# pi_powersupply.net
KiCad netlist of a schematic drawn in Altium Designer
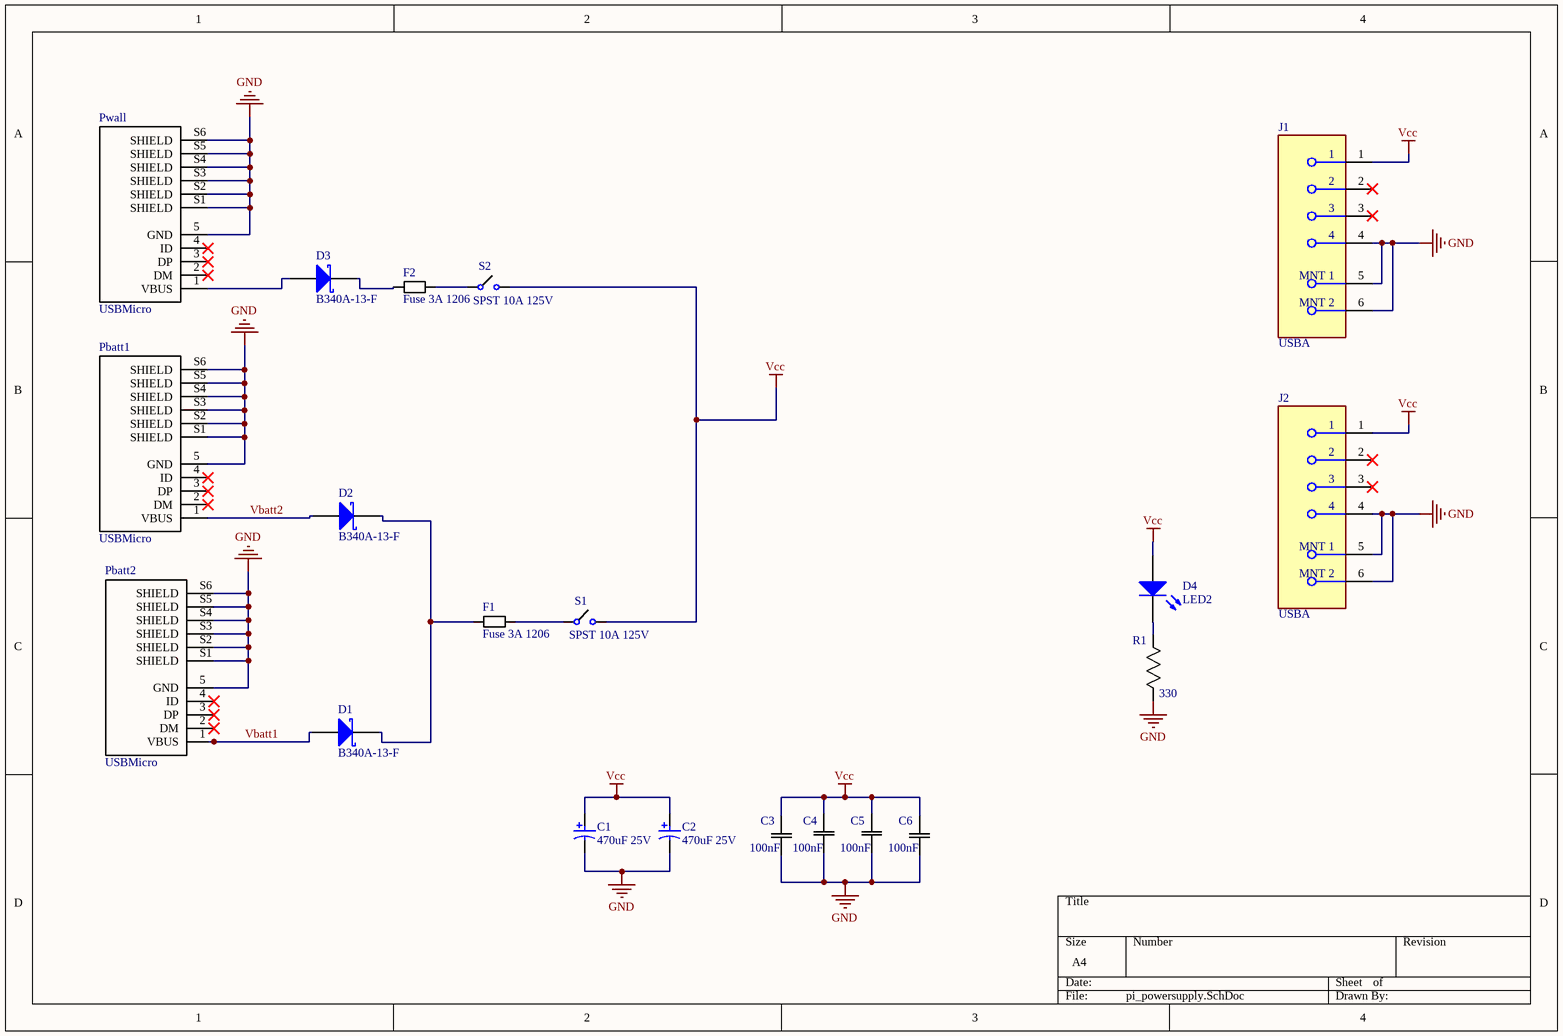
[diagram p0: pi_powersupply.SchDoc]

(export (version "E")
  (design (tool "Eeschema 10.0.6"))
  (components
    (comp (ref "C1")
      (value "470uF 25V")
      (footprint "NIC-CAPA2-10X10_V")
      (fields (field (name "PARTNUMBER") "UUD1E471MNL1GS") (field (name "MANUFACTURER") "Nichicon"))
      (libsource (lib "Altium Content Vault") (part "NIC-CAP-P-2"))
    )
    (comp (ref "C2")
      (value "470uF 25V")
      (footprint "NIC-CAPA2-10X10_V")
      (fields (field (name "PARTNUMBER") "UUD1E471MNL1GS") (field (name "MANUFACTURER") "Nichicon"))
      (libsource (lib "Altium Content Vault") (part "NIC-CAP-P-2"))
    )
    (comp (ref "C3")
      (value "100nF")
      (footprint "0805")
      (description "CAP CER 0.1UF 50V X7R 0805")
      (fields (field (name "MP") "CC0805KRX7R9BB104") (field (name "MF") "Yageo"))
      (libsource (lib "AltiumLibraries") (part "CAP 100nF 0805"))
    )
    (comp (ref "C4")
      (value "100nF")
      (footprint "0805")
      (description "CAP CER 0.1UF 50V X7R 0805")
      (fields (field (name "MP") "CC0805KRX7R9BB104") (field (name "MF") "Yageo"))
      (libsource (lib "AltiumLibraries") (part "CAP 100nF 0805"))
    )
    (comp (ref "C5")
      (value "100nF")
      (footprint "0805")
      (description "CAP CER 0.1UF 50V X7R 0805")
      (fields (field (name "MP") "CC0805KRX7R9BB104") (field (name "MF") "Yageo"))
      (libsource (lib "AltiumLibraries") (part "CAP 100nF 0805"))
    )
    (comp (ref "C6")
      (value "100nF")
      (footprint "0805")
      (description "CAP CER 0.1UF 50V X7R 0805")
      (fields (field (name "MP") "CC0805KRX7R9BB104") (field (name "MF") "Yageo"))
      (libsource (lib "AltiumLibraries") (part "CAP 100nF 0805"))
    )
    (comp (ref "D1")
      (value "B340A-13-F")
      (footprint "DIOD-SMA-2_V")
      (libsource (lib "Altium Content Vault") (part "DSKY-AK-2"))
    )
    (comp (ref "D2")
      (value "B340A-13-F")
      (footprint "DIOD-SMA-2_V")
      (libsource (lib "Altium Content Vault") (part "DSKY-AK-2"))
    )
    (comp (ref "D3")
      (value "B340A-13-F")
      (footprint "DIOD-SMA-2_V")
      (libsource (lib "Altium Content Vault") (part "DSKY-AK-2"))
    )
    (comp (ref "D4")
      (value "LED2")
      (footprint "3.2X1.6X1.1")
      (description "Typical RED, GREEN, YELLOW, AMBER GaAs LED")
      (fields (field (name "MF") "Lite-On Inc.") (field (name "MP") "LTST-C190CKT"))
      (libsource (lib "AltiumLibraries") (part "LED RED SMD"))
    )
    (comp (ref "F1")
      (value "Fuse 3A 1206")
      (footprint "1206")
      (description "FUSE 3.0A 63VAC/DC SLOW 1206")
      (fields (field (name "MF") "Bel Fuse Inc.") (field (name "MP") "0685T3000-01"))
      (libsource (lib "AltiumLibraries") (part "Fuse 3A 1206"))
    )
    (comp (ref "F2")
      (value "Fuse 3A 1206")
      (footprint "1206")
      (description "FUSE 3.0A 63VAC/DC SLOW 1206")
      (fields (field (name "MF") "Bel Fuse Inc.") (field (name "MP") "0685T3000-01"))
      (libsource (lib "AltiumLibraries") (part "Fuse 3A 1206"))
    )
    (comp (ref "J1")
      (value "USBA")
      (footprint "TE_Connectivity_292303-4_MFG")
      (description "CONN RCPT USB2.0 TYPEA 4POS R/A")
      (fields (field (name "PART NUMBER") "292303-4") (field (name "MANUFACTURER") "TE Connectivity"))
      (libsource (lib "Altium Content Vault") (part "292303-4"))
    )
    (comp (ref "J2")
      (value "USBA")
      (footprint "TE_Connectivity_292303-4_MFG")
      (description "CONN RCPT USB2.0 TYPEA 4POS R/A")
      (fields (field (name "PART NUMBER") "292303-4") (field (name "MANUFACTURER") "TE Connectivity"))
      (libsource (lib "Altium Content Vault") (part "292303-4"))
    )
    (comp (ref "Pbatt1")
      (value "USBMicro")
      (footprint "USB Micro B Receptacle")
      (description "USB - micro B USB 2.0 Receptacle Connector 5 Position Surface Mount, Right Angle; Through Hole")
      (fields (field (name "MF") "Amphenol ICC (FCI)") (field (name "MP") "10118194-0001LF"))
      (libsource (lib "AltiumLibraries") (part "USB Micro B Receptacle"))
    )
    (comp (ref "Pbatt2")
      (value "USBMicro")
      (footprint "USB Micro B Receptacle")
      (description "USB - micro B USB 2.0 Receptacle Connector 5 Position Surface Mount, Right Angle; Through Hole")
      (fields (field (name "MF") "Amphenol ICC (FCI)") (field (name "MP") "10118194-0001LF"))
      (libsource (lib "AltiumLibraries") (part "USB Micro B Receptacle"))
    )
    (comp (ref "Pwall")
      (value "USBMicro")
      (footprint "USB Micro B Receptacle")
      (description "USB - micro B USB 2.0 Receptacle Connector 5 Position Surface Mount, Right Angle; Through Hole")
      (fields (field (name "MF") "Amphenol ICC (FCI)") (field (name "MP") "10118194-0001LF"))
      (libsource (lib "AltiumLibraries") (part "USB Micro B Receptacle"))
    )
    (comp (ref "R1")
      (value "330")
      (footprint "0805")
      (description "RES SMD 330 OHM 1% 1/8W 0805")
      (fields (field (name "MP") "RC0805FR-07330RL") (field (name "MF") "Yageo"))
      (libsource (lib "AltiumLibraries") (part "RES 330 0805"))
    )
    (comp (ref "S1")
      (value "SPST 10A 125V")
      (footprint "SWITCH ROCKER SPST 10A 125V")
      (description "Rocker Switch SPST 10A (AC) 125V Panel Mount, Snap-In")
      (fields (field (name "MP") "SRB22A2FBBNN") (field (name "MF") "ZF Electronics"))
      (libsource (lib "AltiumLibraries") (part "SW ROCKER"))
    )
    (comp (ref "S2")
      (value "SPST 10A 125V")
      (footprint "SWITCH ROCKER SPST 10A 125V")
      (description "Rocker Switch SPST 10A (AC) 125V Panel Mount, Snap-In")
      (fields (field (name "MP") "SRB22A2FBBNN") (field (name "MF") "ZF Electronics"))
      (libsource (lib "AltiumLibraries") (part "SW ROCKER"))
    )
  )
  (nets
    (net (code "1") (name "/Vbatt1") (class "Default")
      (node (ref "D1") (pin "1") (pinfunction "A_1") (pintype "passive"))
      (node (ref "Pbatt2") (pin "1") (pinfunction "VBUS_1") (pintype "passive"))
    )
    (net (code "2") (name "/Vbatt2") (class "Default")
      (node (ref "D2") (pin "1") (pinfunction "A_1") (pintype "passive"))
      (node (ref "Pbatt1") (pin "1") (pinfunction "VBUS_1") (pintype "passive"))
    )
    (net (code "3") (name "GND") (class "Default")
      (node (ref "C1") (pin "2") (pinfunction "2_2") (pintype "passive"))
      (node (ref "C2") (pin "2") (pinfunction "2_2") (pintype "passive"))
      (node (ref "C3") (pin "1") (pinfunction "C1_1") (pintype "passive"))
      (node (ref "C4") (pin "1") (pinfunction "C1_1") (pintype "passive"))
      (node (ref "C5") (pin "1") (pinfunction "C1_1") (pintype "passive"))
      (node (ref "C6") (pin "1") (pinfunction "C1_1") (pintype "passive"))
      (node (ref "J1") (pin "4") (pinfunction "4_4") (pintype "passive"))
      (node (ref "J1") (pin "5") (pinfunction "MNT_1_5") (pintype "passive"))
      (node (ref "J1") (pin "6") (pinfunction "MNT_2_6") (pintype "passive"))
      (node (ref "J2") (pin "4") (pinfunction "4_4") (pintype "passive"))
      (node (ref "J2") (pin "5") (pinfunction "MNT_1_5") (pintype "passive"))
      (node (ref "J2") (pin "6") (pinfunction "MNT_2_6") (pintype "passive"))
      (node (ref "Pbatt1") (pin "5") (pinfunction "GND_5") (pintype "passive"))
      (node (ref "Pbatt1") (pin "S1") (pinfunction "SHIELD_S1") (pintype "passive"))
      (node (ref "Pbatt1") (pin "S2") (pinfunction "SHIELD_S2") (pintype "passive"))
      (node (ref "Pbatt1") (pin "S3") (pinfunction "SHIELD_S3") (pintype "passive"))
      (node (ref "Pbatt1") (pin "S4") (pinfunction "SHIELD_S4") (pintype "passive"))
      (node (ref "Pbatt1") (pin "S5") (pinfunction "SHIELD_S5") (pintype "passive"))
      (node (ref "Pbatt1") (pin "S6") (pinfunction "SHIELD_S6") (pintype "passive"))
      (node (ref "Pbatt2") (pin "5") (pinfunction "GND_5") (pintype "passive"))
      (node (ref "Pbatt2") (pin "S1") (pinfunction "SHIELD_S1") (pintype "passive"))
      (node (ref "Pbatt2") (pin "S2") (pinfunction "SHIELD_S2") (pintype "passive"))
      (node (ref "Pbatt2") (pin "S3") (pinfunction "SHIELD_S3") (pintype "passive"))
      (node (ref "Pbatt2") (pin "S4") (pinfunction "SHIELD_S4") (pintype "passive"))
      (node (ref "Pbatt2") (pin "S5") (pinfunction "SHIELD_S5") (pintype "passive"))
      (node (ref "Pbatt2") (pin "S6") (pinfunction "SHIELD_S6") (pintype "passive"))
      (node (ref "Pwall") (pin "5") (pinfunction "GND_5") (pintype "passive"))
      (node (ref "Pwall") (pin "S1") (pinfunction "SHIELD_S1") (pintype "passive"))
      (node (ref "Pwall") (pin "S2") (pinfunction "SHIELD_S2") (pintype "passive"))
      (node (ref "Pwall") (pin "S3") (pinfunction "SHIELD_S3") (pintype "passive"))
      (node (ref "Pwall") (pin "S4") (pinfunction "SHIELD_S4") (pintype "passive"))
      (node (ref "Pwall") (pin "S5") (pinfunction "SHIELD_S5") (pintype "passive"))
      (node (ref "Pwall") (pin "S6") (pinfunction "SHIELD_S6") (pintype "passive"))
      (node (ref "R1") (pin "2") (pinfunction "R2_2") (pintype "passive"))
    )
    (net (code "4") (name "Net-(D1-K)") (class "Default")
      (node (ref "D1") (pin "2") (pinfunction "K_2") (pintype "passive"))
      (node (ref "D2") (pin "2") (pinfunction "K_2") (pintype "passive"))
      (node (ref "F1") (pin "1") (pinfunction "1_1") (pintype "passive"))
    )
    (net (code "5") (name "Net-(D3-A)") (class "Default")
      (node (ref "D3") (pin "1") (pinfunction "A_1") (pintype "passive"))
      (node (ref "Pwall") (pin "1") (pinfunction "VBUS_1") (pintype "passive"))
    )
    (net (code "6") (name "Net-(D3-K)") (class "Default")
      (node (ref "D3") (pin "2") (pinfunction "K_2") (pintype "passive"))
      (node (ref "F2") (pin "1") (pinfunction "1_1") (pintype "passive"))
    )
    (net (code "7") (name "Net-(D4-K)") (class "Default")
      (node (ref "D4") (pin "2") (pinfunction "K_2") (pintype "passive"))
      (node (ref "R1") (pin "1") (pinfunction "R1_1") (pintype "passive"))
    )
    (net (code "8") (name "Net-(F1-Pad2)") (class "Default")
      (node (ref "F1") (pin "2") (pinfunction "2_2") (pintype "passive"))
      (node (ref "S1") (pin "0") (pinfunction "0_0") (pintype "passive"))
    )
    (net (code "9") (name "Net-(F2-Pad2)") (class "Default")
      (node (ref "F2") (pin "2") (pinfunction "2_2") (pintype "passive"))
      (node (ref "S2") (pin "0") (pinfunction "0_0") (pintype "passive"))
    )
    (net (code "10") (name "Vcc") (class "Default")
      (node (ref "C1") (pin "1") (pinfunction "1_1") (pintype "passive"))
      (node (ref "C2") (pin "1") (pinfunction "1_1") (pintype "passive"))
      (node (ref "C3") (pin "2") (pinfunction "C2_2") (pintype "passive"))
      (node (ref "C4") (pin "2") (pinfunction "C2_2") (pintype "passive"))
      (node (ref "C5") (pin "2") (pinfunction "C2_2") (pintype "passive"))
      (node (ref "C6") (pin "2") (pinfunction "C2_2") (pintype "passive"))
      (node (ref "D4") (pin "1") (pinfunction "A_1") (pintype "passive"))
      (node (ref "J1") (pin "1") (pinfunction "1_1") (pintype "passive"))
      (node (ref "J2") (pin "1") (pinfunction "1_1") (pintype "passive"))
      (node (ref "S1") (pin "1") (pinfunction "1_1") (pintype "passive"))
      (node (ref "S2") (pin "1") (pinfunction "1_1") (pintype "passive"))
    )
    (net (code "11") (name "unconnected-(J1-Pad2)") (class "Default")
      (node (ref "J1") (pin "2") (pinfunction "2_2") (pintype "passive+no_connect"))
    )
    (net (code "12") (name "unconnected-(J1-Pad3)") (class "Default")
      (node (ref "J1") (pin "3") (pinfunction "3_3") (pintype "passive+no_connect"))
    )
    (net (code "13") (name "unconnected-(J2-Pad2)") (class "Default")
      (node (ref "J2") (pin "2") (pinfunction "2_2") (pintype "passive+no_connect"))
    )
    (net (code "14") (name "unconnected-(J2-Pad3)") (class "Default")
      (node (ref "J2") (pin "3") (pinfunction "3_3") (pintype "passive+no_connect"))
    )
    (net (code "15") (name "unconnected-(Pbatt1-DM-Pad2)") (class "Default")
      (node (ref "Pbatt1") (pin "2") (pinfunction "DM_2") (pintype "passive+no_connect"))
    )
    (net (code "16") (name "unconnected-(Pbatt1-DP-Pad3)") (class "Default")
      (node (ref "Pbatt1") (pin "3") (pinfunction "DP_3") (pintype "passive+no_connect"))
    )
    (net (code "17") (name "unconnected-(Pbatt1-ID-Pad4)") (class "Default")
      (node (ref "Pbatt1") (pin "4") (pinfunction "ID_4") (pintype "passive+no_connect"))
    )
    (net (code "18") (name "unconnected-(Pbatt2-DM-Pad2)") (class "Default")
      (node (ref "Pbatt2") (pin "2") (pinfunction "DM_2") (pintype "passive+no_connect"))
    )
    (net (code "19") (name "unconnected-(Pbatt2-DP-Pad3)") (class "Default")
      (node (ref "Pbatt2") (pin "3") (pinfunction "DP_3") (pintype "passive+no_connect"))
    )
    (net (code "20") (name "unconnected-(Pbatt2-ID-Pad4)") (class "Default")
      (node (ref "Pbatt2") (pin "4") (pinfunction "ID_4") (pintype "passive+no_connect"))
    )
    (net (code "21") (name "unconnected-(Pwall-DM-Pad2)") (class "Default")
      (node (ref "Pwall") (pin "2") (pinfunction "DM_2") (pintype "passive+no_connect"))
    )
    (net (code "22") (name "unconnected-(Pwall-DP-Pad3)") (class "Default")
      (node (ref "Pwall") (pin "3") (pinfunction "DP_3") (pintype "passive+no_connect"))
    )
    (net (code "23") (name "unconnected-(Pwall-ID-Pad4)") (class "Default")
      (node (ref "Pwall") (pin "4") (pinfunction "ID_4") (pintype "passive+no_connect"))
    )
  )
)
